# feeder-meteo-clock.net
KiCad netlist of a schematic drawn in EAGLE
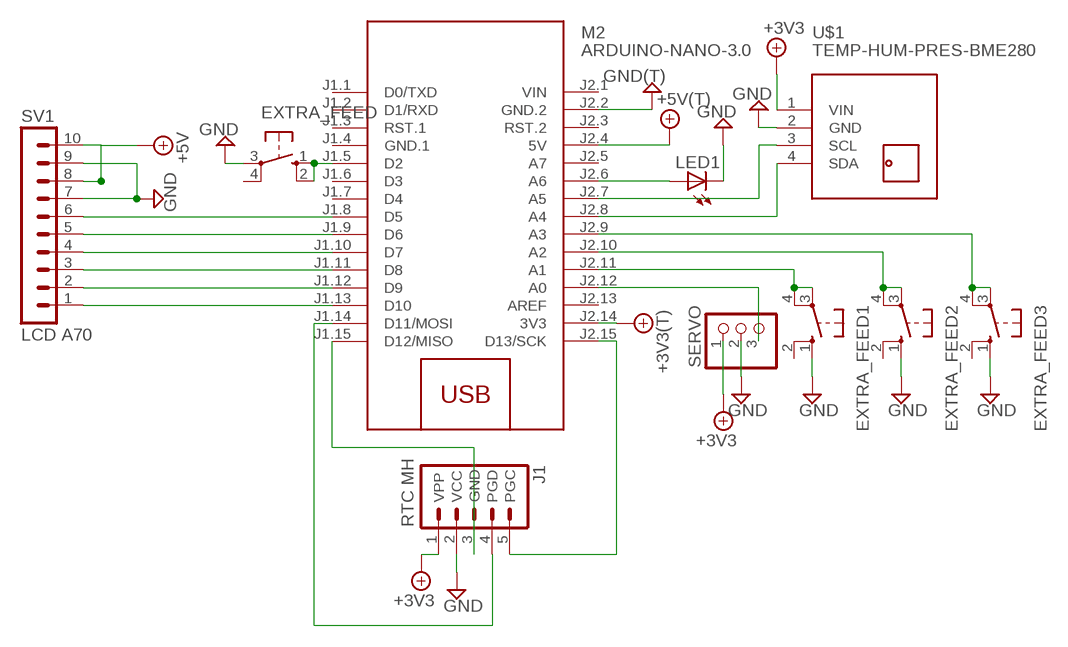
[diagram p0: schematic, sheet 1]

(export (version "E")
  (design (tool "Eeschema 10.0.6"))
  (components
    (comp (ref "+3V1")
      (value "+3V3(T)")
      (footprint "eagle-import:SQUARE")
      (libsource (lib "eagle-import") (part "+18V(T)"))
    )
    (comp (ref "+9V1")
      (value "+5V(T)")
      (footprint "eagle-import:SQUARE")
      (libsource (lib "eagle-import") (part "+9V(T)"))
    )
    (comp (ref "EXTRA_FEED")
      (value "10-XX")
      (footprint "eagle-import:B3F-10XX")
      (fields (field (name "MPN") "B3F-1000"))
      (libsource (lib "eagle-import") (part "10-XX"))
    )
    (comp (ref "EXTRA_FEED1")
      (value "10-XX")
      (footprint "eagle-import:B3F-10XX")
      (fields (field (name "MPN") "B3F-1000"))
      (libsource (lib "eagle-import") (part "10-XX"))
    )
    (comp (ref "EXTRA_FEED2")
      (value "10-XX")
      (footprint "eagle-import:B3F-10XX")
      (fields (field (name "MPN") "B3F-1000"))
      (libsource (lib "eagle-import") (part "10-XX"))
    )
    (comp (ref "EXTRA_FEED3")
      (value "10-XX")
      (footprint "eagle-import:B3F-10XX")
      (fields (field (name "MPN") "B3F-1000"))
      (libsource (lib "eagle-import") (part "10-XX"))
    )
    (comp (ref "GND1")
      (value "GND(T)")
      (footprint "eagle-import:SQUARE")
      (libsource (lib "eagle-import") (part "GND(T)"))
    )
    (comp (ref "J1")
      (value "RTC MH")
      (footprint "eagle-import:PIC_ICSP_MINI_5_PIN")
      (libsource (lib "eagle-import") (part "PIC_ICSP_MINI_5_PIN"))
    )
    (comp (ref "LED1")
      (value "LED3MM")
      (footprint "eagle-import:LED3MM")
      (libsource (lib "eagle-import") (part "LED3MM"))
    )
    (comp (ref "M2")
      (value "ARDUINO-NANO-3.0")
      (footprint "eagle-import:ARDUINO-NANO-3.0")
      (libsource (lib "eagle-import") (part "ARDUINO-NANO-3.0"))
    )
    (comp (ref "SERVO")
      (value "PINHD-1X3")
      (footprint "eagle-import:1X03")
      (libsource (lib "eagle-import") (part "PINHD-1X3"))
    )
    (comp (ref "SV1")
      (value "LCD A70")
      (footprint "eagle-import:MA10-1")
      (libsource (lib "eagle-import") (part "MA10-1"))
    )
    (comp (ref "U$1")
      (value "TEMP-HUM-PRES-BME280")
      (footprint "eagle-import:TEMP-HUM-PRES-BME280")
      (libsource (lib "eagle-import") (part "TEMP-HUM-PRES-BME280"))
    )
  )
  (nets
    (net (code "1") (name "+3V3") (class "Default")
      (node (ref "+3V1") (pin "1") (pinfunction "+18V_1") (pintype "power_in"))
      (node (ref "J1") (pin "1") (pinfunction "VPP_1") (pintype "passive"))
      (node (ref "M2") (pin "J2.14") (pinfunction "3V3_J2.14") (pintype "power_in"))
      (node (ref "SERVO") (pin "1") (pinfunction "1_1") (pintype "passive"))
      (node (ref "U$1") (pin "1") (pinfunction "VIN_1") (pintype "power_in"))
    )
    (net (code "2") (name "+5V") (class "Default")
      (node (ref "+9V1") (pin "1") (pinfunction "+9V_1") (pintype "power_in"))
      (node (ref "M2") (pin "J2.4") (pinfunction "5V_J2.4") (pintype "power_in"))
      (node (ref "SV1") (pin "10") (pinfunction "10_10") (pintype "passive"))
      (node (ref "SV1") (pin "8") (pinfunction "8_8") (pintype "passive"))
    )
    (net (code "3") (name "/GND.1") (class "Default")
      (node (ref "M2") (pin "J1.4") (pinfunction "GND.1_J1.4") (pintype "power_in"))
    )
    (net (code "4") (name "/VIN") (class "Default")
      (node (ref "M2") (pin "J2.1") (pinfunction "VIN_J2.1") (pintype "power_in"))
    )
    (net (code "5") (name "GND") (class "Default")
      (node (ref "EXTRA_FEED") (pin "3") (pinfunction "P_3") (pintype "passive"))
      (node (ref "EXTRA_FEED1") (pin "1") (pinfunction "S_1") (pintype "passive"))
      (node (ref "EXTRA_FEED2") (pin "1") (pinfunction "S_1") (pintype "passive"))
      (node (ref "EXTRA_FEED3") (pin "1") (pinfunction "S_1") (pintype "passive"))
      (node (ref "GND1") (pin "1") (pinfunction "GND_1") (pintype "power_in"))
      (node (ref "J1") (pin "2") (pinfunction "VCC_2") (pintype "passive"))
      (node (ref "LED1") (pin "K") (pinfunction "C_K") (pintype "passive"))
      (node (ref "M2") (pin "J2.2") (pinfunction "GND.2_J2.2") (pintype "power_in"))
      (node (ref "SERVO") (pin "2") (pinfunction "2_2") (pintype "passive"))
      (node (ref "SV1") (pin "7") (pinfunction "7_7") (pintype "passive"))
      (node (ref "SV1") (pin "9") (pinfunction "9_9") (pintype "passive"))
      (node (ref "U$1") (pin "2") (pinfunction "GND_2") (pintype "power_in"))
    )
    (net (code "6") (name "Net-(EXTRA_FEED-S)") (class "Default")
      (node (ref "EXTRA_FEED") (pin "1") (pinfunction "S_1") (pintype "passive"))
      (node (ref "EXTRA_FEED") (pin "2") (pinfunction "S1_2") (pintype "passive"))
      (node (ref "M2") (pin "J1.5") (pinfunction "D2_J1.5") (pintype "bidirectional"))
    )
    (net (code "7") (name "Net-(EXTRA_FEED1-P)") (class "Default")
      (node (ref "EXTRA_FEED1") (pin "3") (pinfunction "P_3") (pintype "passive"))
      (node (ref "EXTRA_FEED1") (pin "4") (pinfunction "P1_4") (pintype "passive"))
      (node (ref "M2") (pin "J2.11") (pinfunction "A1_J2.11") (pintype "bidirectional"))
    )
    (net (code "8") (name "Net-(EXTRA_FEED2-P)") (class "Default")
      (node (ref "EXTRA_FEED2") (pin "3") (pinfunction "P_3") (pintype "passive"))
      (node (ref "EXTRA_FEED2") (pin "4") (pinfunction "P1_4") (pintype "passive"))
      (node (ref "M2") (pin "J2.10") (pinfunction "A2_J2.10") (pintype "bidirectional"))
    )
    (net (code "9") (name "Net-(EXTRA_FEED3-P)") (class "Default")
      (node (ref "EXTRA_FEED3") (pin "3") (pinfunction "P_3") (pintype "passive"))
      (node (ref "EXTRA_FEED3") (pin "4") (pinfunction "P1_4") (pintype "passive"))
      (node (ref "M2") (pin "J2.9") (pinfunction "A3_J2.9") (pintype "bidirectional"))
    )
    (net (code "10") (name "Net-(J1-GND)") (class "Default")
      (node (ref "J1") (pin "3") (pinfunction "GND_3") (pintype "passive"))
      (node (ref "M2") (pin "J1.15") (pinfunction "D12/MISO_J1.15") (pintype "bidirectional"))
    )
    (net (code "11") (name "Net-(J1-PGC)") (class "Default")
      (node (ref "J1") (pin "5") (pinfunction "PGC_5") (pintype "passive"))
      (node (ref "M2") (pin "J2.15") (pinfunction "D13/SCK_J2.15") (pintype "bidirectional"))
    )
    (net (code "12") (name "Net-(J1-PGD)") (class "Default")
      (node (ref "J1") (pin "4") (pinfunction "PGD_4") (pintype "passive"))
      (node (ref "M2") (pin "J1.14") (pinfunction "D11/MOSI_J1.14") (pintype "bidirectional"))
    )
    (net (code "13") (name "Net-(M2-A0)") (class "Default")
      (node (ref "M2") (pin "J2.12") (pinfunction "A0_J2.12") (pintype "bidirectional"))
      (node (ref "SERVO") (pin "3") (pinfunction "3_3") (pintype "passive"))
    )
    (net (code "14") (name "Net-(M2-A4)") (class "Default")
      (node (ref "M2") (pin "J2.8") (pinfunction "A4_J2.8") (pintype "bidirectional"))
      (node (ref "U$1") (pin "4") (pinfunction "SDA_4") (pintype "bidirectional"))
    )
    (net (code "15") (name "Net-(M2-A5)") (class "Default")
      (node (ref "M2") (pin "J2.7") (pinfunction "A5_J2.7") (pintype "bidirectional"))
      (node (ref "U$1") (pin "3") (pinfunction "SCL_3") (pintype "bidirectional"))
    )
    (net (code "16") (name "Net-(M2-A6)") (class "Default")
      (node (ref "LED1") (pin "A") (pinfunction "A_A") (pintype "passive"))
      (node (ref "M2") (pin "J2.6") (pinfunction "A6_J2.6") (pintype "bidirectional"))
    )
    (net (code "17") (name "Net-(M2-D5)") (class "Default")
      (node (ref "M2") (pin "J1.8") (pinfunction "D5_J1.8") (pintype "bidirectional"))
      (node (ref "SV1") (pin "6") (pinfunction "6_6") (pintype "passive"))
    )
    (net (code "18") (name "Net-(M2-D6)") (class "Default")
      (node (ref "M2") (pin "J1.9") (pinfunction "D6_J1.9") (pintype "bidirectional"))
      (node (ref "SV1") (pin "5") (pinfunction "5_5") (pintype "passive"))
    )
    (net (code "19") (name "Net-(M2-D7)") (class "Default")
      (node (ref "M2") (pin "J1.10") (pinfunction "D7_J1.10") (pintype "bidirectional"))
      (node (ref "SV1") (pin "4") (pinfunction "4_4") (pintype "passive"))
    )
    (net (code "20") (name "Net-(M2-D8)") (class "Default")
      (node (ref "M2") (pin "J1.11") (pinfunction "D8_J1.11") (pintype "bidirectional"))
      (node (ref "SV1") (pin "3") (pinfunction "3_3") (pintype "passive"))
    )
    (net (code "21") (name "Net-(M2-D9)") (class "Default")
      (node (ref "M2") (pin "J1.12") (pinfunction "D9_J1.12") (pintype "bidirectional"))
      (node (ref "SV1") (pin "2") (pinfunction "2_2") (pintype "passive"))
    )
    (net (code "22") (name "Net-(M2-D10)") (class "Default")
      (node (ref "M2") (pin "J1.13") (pinfunction "D10_J1.13") (pintype "bidirectional"))
      (node (ref "SV1") (pin "1") (pinfunction "1_1") (pintype "passive"))
    )
    (net (code "23") (name "unconnected-(EXTRA_FEED-P1-Pad4)") (class "Default")
      (node (ref "EXTRA_FEED") (pin "4") (pinfunction "P1_4") (pintype "passive"))
    )
    (net (code "24") (name "unconnected-(EXTRA_FEED1-S1-Pad2)") (class "Default")
      (node (ref "EXTRA_FEED1") (pin "2") (pinfunction "S1_2") (pintype "passive"))
    )
    (net (code "25") (name "unconnected-(EXTRA_FEED2-S1-Pad2)") (class "Default")
      (node (ref "EXTRA_FEED2") (pin "2") (pinfunction "S1_2") (pintype "passive"))
    )
    (net (code "26") (name "unconnected-(EXTRA_FEED3-S1-Pad2)") (class "Default")
      (node (ref "EXTRA_FEED3") (pin "2") (pinfunction "S1_2") (pintype "passive"))
    )
    (net (code "27") (name "unconnected-(M2-A7-PadJ2.5)") (class "Default")
      (node (ref "M2") (pin "J2.5") (pinfunction "A7_J2.5") (pintype "bidirectional"))
    )
    (net (code "28") (name "unconnected-(M2-AREF-PadJ2.13)") (class "Default")
      (node (ref "M2") (pin "J2.13") (pinfunction "AREF_J2.13") (pintype "bidirectional"))
    )
    (net (code "29") (name "unconnected-(M2-D0{slash}TXD-PadJ1.1)") (class "Default")
      (node (ref "M2") (pin "J1.1") (pinfunction "D0/TXD_J1.1") (pintype "bidirectional"))
    )
    (net (code "30") (name "unconnected-(M2-D1{slash}RXD-PadJ1.2)") (class "Default")
      (node (ref "M2") (pin "J1.2") (pinfunction "D1/RXD_J1.2") (pintype "bidirectional"))
    )
    (net (code "31") (name "unconnected-(M2-D3-PadJ1.6)") (class "Default")
      (node (ref "M2") (pin "J1.6") (pinfunction "D3_J1.6") (pintype "bidirectional"))
    )
    (net (code "32") (name "unconnected-(M2-D4-PadJ1.7)") (class "Default")
      (node (ref "M2") (pin "J1.7") (pinfunction "D4_J1.7") (pintype "bidirectional"))
    )
    (net (code "33") (name "unconnected-(M2-RST.1-PadJ1.3)") (class "Default")
      (node (ref "M2") (pin "J1.3") (pinfunction "RST.1_J1.3") (pintype "bidirectional"))
    )
    (net (code "34") (name "unconnected-(M2-RST.2-PadJ2.3)") (class "Default")
      (node (ref "M2") (pin "J2.3") (pinfunction "RST.2_J2.3") (pintype "bidirectional"))
    )
  )
)
